# connector_board.net
KiCad netlist of a schematic drawn in EAGLE
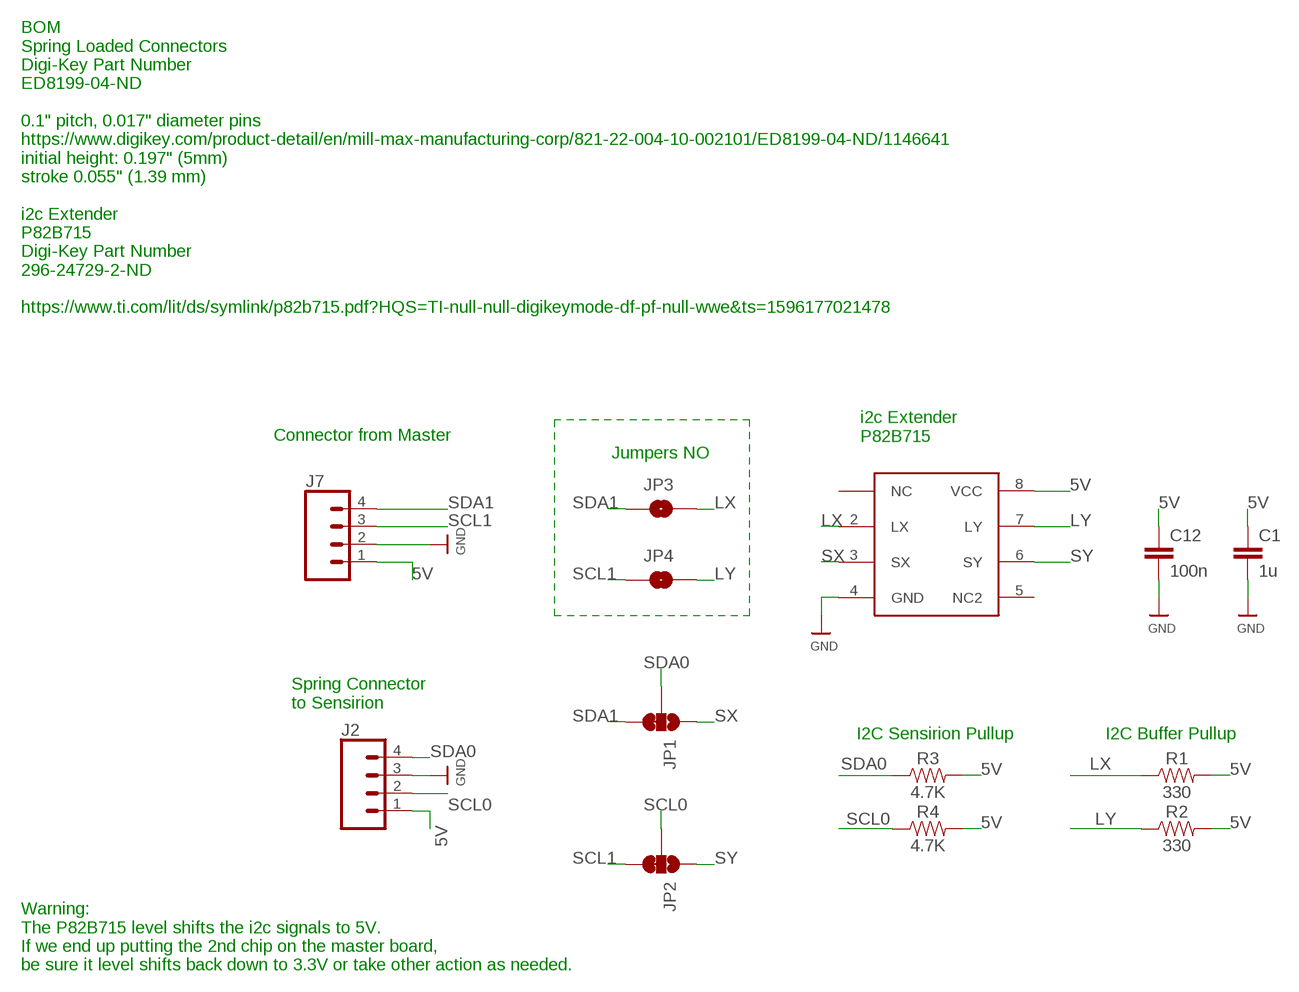
[diagram p0: schematic, sheet 1]

(export (version "E")
  (design (tool "Eeschema 10.0.6"))
  (components
    (comp (ref "C1")
      (value "1u")
      (footprint "eagle-import:0805")
      (libsource (lib "eagle-import") (part "CAP-0805"))
    )
    (comp (ref "C12")
      (value "100n")
      (footprint "eagle-import:0805")
      (libsource (lib "eagle-import") (part "CAP-0805"))
    )
    (comp (ref "J2")
      (value "CONN_0430MILL_DIA")
      (footprint "eagle-import:1X04_30MILL_DIA")
      (libsource (lib "eagle-import") (part "CONN_0430MILL_DIA"))
    )
    (comp (ref "J7")
      (value "CONN_043.5MM_RA")
      (footprint "eagle-import:1X04_3.5MM_RA")
      (libsource (lib "eagle-import") (part "CONN_043.5MM_RA"))
    )
    (comp (ref "JP1")
      (value "JUMPER-SMT_3_1-NC_TRACE_NO-SILK")
      (footprint "eagle-import:SMT-JUMPER_3_1-NC_TRACE_NO-SILK")
      (libsource (lib "eagle-import") (part "JUMPER-SMT_3_1-NC_TRACE_NO-SILK"))
    )
    (comp (ref "JP2")
      (value "JUMPER-SMT_3_1-NC_TRACE_NO-SILK")
      (footprint "eagle-import:SMT-JUMPER_3_1-NC_TRACE_NO-SILK")
      (libsource (lib "eagle-import") (part "JUMPER-SMT_3_1-NC_TRACE_NO-SILK"))
    )
    (comp (ref "JP3")
      (value "JUMPER-SMT_2_NO_SILK")
      (footprint "eagle-import:SMT-JUMPER_2_NO_SILK")
      (libsource (lib "eagle-import") (part "JUMPER-SMT_2_NO_SILK"))
    )
    (comp (ref "JP4")
      (value "JUMPER-SMT_2_NO_SILK")
      (footprint "eagle-import:SMT-JUMPER_2_NO_SILK")
      (libsource (lib "eagle-import") (part "JUMPER-SMT_2_NO_SILK"))
    )
    (comp (ref "R1")
      (value "330")
      (footprint "eagle-import:0805")
      (libsource (lib "eagle-import") (part "0.3OHM-0805-1/8W-1%"))
    )
    (comp (ref "R2")
      (value "330")
      (footprint "eagle-import:0805")
      (libsource (lib "eagle-import") (part "0.3OHM-0805-1/8W-1%"))
    )
    (comp (ref "R3")
      (value "4.7K")
      (footprint "eagle-import:0805")
      (libsource (lib "eagle-import") (part "0.3OHM-0805-1/8W-1%"))
    )
    (comp (ref "R4")
      (value "4.7K")
      (footprint "eagle-import:0805")
      (libsource (lib "eagle-import") (part "0.3OHM-0805-1/8W-1%"))
    )
    (comp (ref "U$2")
      (value "P82B715")
      (footprint "eagle-import:SOIC8")
      (libsource (lib "eagle-import") (part "P82B715"))
    )
  )
  (nets
    (net (code "1") (name "/5V") (class "Default")
      (node (ref "C1") (pin "1") (pinfunction "1_1") (pintype "passive"))
      (node (ref "C12") (pin "1") (pinfunction "1_1") (pintype "passive"))
      (node (ref "J2") (pin "1") (pinfunction "1_1") (pintype "passive"))
      (node (ref "J7") (pin "1") (pinfunction "1_1") (pintype "passive"))
      (node (ref "R1") (pin "2") (pinfunction "2_2") (pintype "passive"))
      (node (ref "R2") (pin "2") (pinfunction "2_2") (pintype "passive"))
      (node (ref "R3") (pin "2") (pinfunction "2_2") (pintype "passive"))
      (node (ref "R4") (pin "2") (pinfunction "2_2") (pintype "passive"))
      (node (ref "U$2") (pin "8") (pinfunction "VCC_8") (pintype "bidirectional"))
    )
    (net (code "2") (name "/LX") (class "Default")
      (node (ref "JP3") (pin "2") (pinfunction "2_2") (pintype "passive"))
      (node (ref "R1") (pin "1") (pinfunction "1_1") (pintype "passive"))
      (node (ref "U$2") (pin "2") (pinfunction "LX_2") (pintype "bidirectional"))
    )
    (net (code "3") (name "/LY") (class "Default")
      (node (ref "JP4") (pin "2") (pinfunction "2_2") (pintype "passive"))
      (node (ref "R2") (pin "1") (pinfunction "1_1") (pintype "passive"))
      (node (ref "U$2") (pin "7") (pinfunction "LY_7") (pintype "bidirectional"))
    )
    (net (code "4") (name "/SCL0") (class "Default")
      (node (ref "J2") (pin "2") (pinfunction "2_2") (pintype "passive"))
      (node (ref "JP2") (pin "2") (pinfunction "2_2") (pintype "passive"))
      (node (ref "R4") (pin "1") (pinfunction "1_1") (pintype "passive"))
    )
    (net (code "5") (name "/SCL1") (class "Default")
      (node (ref "J7") (pin "3") (pinfunction "3_3") (pintype "passive"))
      (node (ref "JP2") (pin "3") (pinfunction "3_3") (pintype "passive"))
      (node (ref "JP4") (pin "1") (pinfunction "1_1") (pintype "passive"))
    )
    (net (code "6") (name "/SDA0") (class "Default")
      (node (ref "J2") (pin "4") (pinfunction "4_4") (pintype "passive"))
      (node (ref "JP1") (pin "2") (pinfunction "2_2") (pintype "passive"))
      (node (ref "R3") (pin "1") (pinfunction "1_1") (pintype "passive"))
    )
    (net (code "7") (name "/SDA1") (class "Default")
      (node (ref "J7") (pin "4") (pinfunction "4_4") (pintype "passive"))
      (node (ref "JP1") (pin "3") (pinfunction "3_3") (pintype "passive"))
      (node (ref "JP3") (pin "1") (pinfunction "1_1") (pintype "passive"))
    )
    (net (code "8") (name "/SX") (class "Default")
      (node (ref "JP1") (pin "1") (pinfunction "1_1") (pintype "passive"))
      (node (ref "U$2") (pin "3") (pinfunction "SX_3") (pintype "bidirectional"))
    )
    (net (code "9") (name "/SY") (class "Default")
      (node (ref "JP2") (pin "1") (pinfunction "1_1") (pintype "passive"))
      (node (ref "U$2") (pin "6") (pinfunction "SY_6") (pintype "bidirectional"))
    )
    (net (code "10") (name "GND") (class "Default")
      (node (ref "C1") (pin "2") (pinfunction "2_2") (pintype "passive"))
      (node (ref "C12") (pin "2") (pinfunction "2_2") (pintype "passive"))
      (node (ref "J2") (pin "3") (pinfunction "3_3") (pintype "passive"))
      (node (ref "J7") (pin "2") (pinfunction "2_2") (pintype "passive"))
      (node (ref "U$2") (pin "4") (pinfunction "GND_4") (pintype "bidirectional"))
    )
    (net (code "11") (name "unconnected-(U$2-NC-Pad1)") (class "Default")
      (node (ref "U$2") (pin "1") (pinfunction "NC_1") (pintype "bidirectional"))
    )
    (net (code "12") (name "unconnected-(U$2-NC2-Pad5)") (class "Default")
      (node (ref "U$2") (pin "5") (pinfunction "NC2_5") (pintype "bidirectional"))
    )
  )
)
